# RPI_3_Backpower.net
KiCad netlist of a schematic drawn in Altium Designer
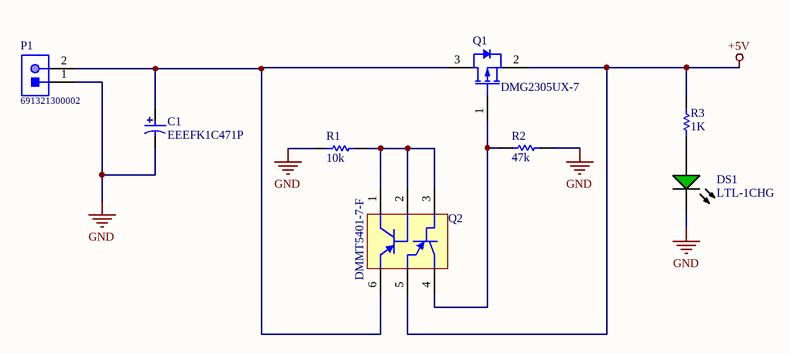
[diagram p0: RPI 3 Backpower.SchDoc]

(export (version "E")
  (design (tool "Eeschema 10.0.6"))
  (components
    (comp (ref "C1")
      (value "EEEFK1C471P")
      (footprint "PNSC-FK-V-F_V")
      (fields (field (name "MANUFACTURER") "Panasonic"))
      (libsource (lib "Altium Content Vault") (part "CAP-P-2"))
    )
    (comp (ref "DS1")
      (value "LTL-1CHG")
      (footprint "LTST-LTL-1CHG-2")
      (description "LITE-ON Electronic, INC, 120 mA, 100 mW, 5 V, -55 to 100 degC, 2-Pin THD, RoHS, Bulk")
      (libsource (lib "Altium Content Vault") (part "LED_GREEN_A1K2-2"))
    )
    (comp (ref "P1")
      (value "691321300002")
      (footprint "691321300002")
      (description "Serie 321 - 3.81mm Vertical PCB Header WR-TBL, 2 pin")
      (fields (field (name "MANUFACTURER") "Wurth Elektronik") (field (name "PUBLISHER") "WurthElektronik"))
      (libsource (lib "Altium Content Vault") (part "WE-CN-1P-M-R2"))
    )
    (comp (ref "Q1")
      (value "DMG2305UX-7")
      (footprint "DIOD-SOT23-3_A_V")
      (description "P-Channel Enhancement Mode MOSFET, 20 V, -55 to 150 degC, 3-Pin SOT23, RoHS, Tape and Reel")
      (libsource (lib "Altium Content Vault") (part "PEMOS-GSD-3"))
    )
    (comp (ref "Q2")
      (value "DMMT5401-7-F")
      (footprint "DIOD-SOT-26-6_N")
      (fields (field (name "TOLERANCE") "1%"))
      (libsource (lib "Altium Content Vault") (part "DIOD-DMMT5401-SOT-26-6"))
    )
    (comp (ref "R1")
      (value "10k")
      (footprint "RESC1609X55X30LL15T15")
      (description "Chip Resistor, 10 KOhm, +/- 1%, 0.1 W, -55 to 155 degC, 0603 (1608 Metric), RoHS, Tape and Reel")
      (fields (field (name "TOLERANCE") "1%") (field (name "MANUFACTURER") "Panasonic"))
      (libsource (lib "Altium Content Vault") (part "RES-2"))
    )
    (comp (ref "R2")
      (value "47k")
      (footprint "RESC1608X55X25LL10T15")
      (fields (field (name "MANUFACTURER") "Yageo") (field (name "PART NUMBER") "AC0603FR-0747KL"))
      (libsource (lib "Altium Content Vault") (part "RES"))
    )
    (comp (ref "R3")
      (value "1K")
      (footprint "RESC1608X55X30LL15T15")
      (fields (field (name "PART NUMBER") "ERJ-3EKF1001V") (field (name "MANUFACTURER") "Panasonic"))
      (libsource (lib "Altium Content Vault") (part "RES"))
    )
  )
  (nets
    (net (code "1") (name "+5V") (class "Default")
      (node (ref "Q1") (pin "2") (pinfunction "SOURCE_2") (pintype "passive"))
      (node (ref "Q2") (pin "5") (pinfunction "E2_5") (pintype "passive"))
      (node (ref "R3") (pin "2") (pinfunction "2_2") (pintype "passive"))
    )
    (net (code "2") (name "GND") (class "Default")
      (node (ref "C1") (pin "2") (pinfunction "2_2") (pintype "passive"))
      (node (ref "DS1") (pin "2") (pinfunction "K_2") (pintype "passive"))
      (node (ref "P1") (pin "1") (pinfunction "1_1") (pintype "passive"))
      (node (ref "R1") (pin "1") (pinfunction "1_1") (pintype "passive"))
      (node (ref "R2") (pin "1") (pinfunction "1_1") (pintype "passive"))
    )
    (net (code "3") (name "Net-(DS1-A)") (class "Default")
      (node (ref "DS1") (pin "1") (pinfunction "A_1") (pintype "passive"))
      (node (ref "R3") (pin "1") (pinfunction "1_1") (pintype "passive"))
    )
    (net (code "4") (name "Net-(Q1-DRAIN)") (class "Default")
      (node (ref "C1") (pin "1") (pinfunction "1_1") (pintype "passive"))
      (node (ref "P1") (pin "2") (pinfunction "2_2") (pintype "passive"))
      (node (ref "Q1") (pin "3") (pinfunction "DRAIN_3") (pintype "passive"))
      (node (ref "Q2") (pin "6") (pinfunction "E1_6") (pintype "passive"))
    )
    (net (code "5") (name "Net-(Q1-GATE)") (class "Default")
      (node (ref "Q1") (pin "1") (pinfunction "GATE_1") (pintype "passive"))
      (node (ref "Q2") (pin "4") (pinfunction "C2_4") (pintype "passive"))
      (node (ref "R2") (pin "2") (pinfunction "2_2") (pintype "passive"))
    )
    (net (code "6") (name "Net-(Q2-B1)") (class "Default")
      (node (ref "Q2") (pin "1") (pinfunction "C1_1") (pintype "passive"))
      (node (ref "Q2") (pin "2") (pinfunction "B1_2") (pintype "passive"))
      (node (ref "Q2") (pin "3") (pinfunction "B2_3") (pintype "passive"))
      (node (ref "R1") (pin "2") (pinfunction "2_2") (pintype "passive"))
    )
  )
)
